# rc_switch_dualsided_with_fet_driver_2.net
KiCad netlist of a schematic drawn in EAGLE
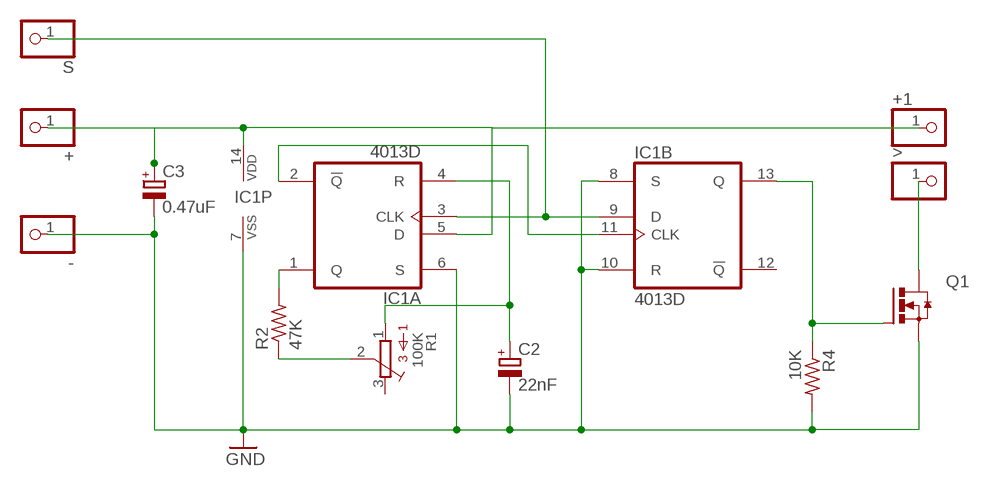
[diagram p0: schematic, sheet 1]

(export (version "E")
  (design (tool "Eeschema 10.0.6"))
  (components
    (comp (ref "+")
      (value "PINHD-1X1")
      (footprint "eagle-import:1X01")
      (libsource (lib "eagle-import") (part "PINHD-1X1"))
    )
    (comp (ref "+1")
      (value "PINHD-1X1")
      (footprint "eagle-import:1X01")
      (libsource (lib "eagle-import") (part "PINHD-1X1"))
    )
    (comp (ref "-")
      (value "PINHD-1X1")
      (footprint "eagle-import:1X01")
      (libsource (lib "eagle-import") (part "PINHD-1X1"))
    )
    (comp (ref ">")
      (value "PINHD-1X1")
      (footprint "eagle-import:1X01")
      (libsource (lib "eagle-import") (part "PINHD-1X1"))
    )
    (comp (ref "C2")
      (value "22nF")
      (footprint "eagle-import:PANASONIC_A")
      (libsource (lib "eagle-import") (part "CPOL-EUA"))
    )
    (comp (ref "C3")
      (value "0.47uF")
      (footprint "eagle-import:PANASONIC_A")
      (libsource (lib "eagle-import") (part "CPOL-EUA"))
    )
    (comp (ref "IC1")
      (value "4013D")
      (footprint "eagle-import:SO14")
      (libsource (lib "eagle-import") (part "4013D"))
    )
    (comp (ref "Q1")
      (value "HUF76629D3ST_F085D-PAK_TO252")
      (footprint "eagle-import:D-PAK_TO252")
      (libsource (lib "eagle-import") (part "HUF76629D3ST_F085D-PAK_TO252"))
    )
    (comp (ref "R1")
      (value "100K")
      (footprint "eagle-import:3386P")
      (libsource (lib "eagle-import") (part "3386-P"))
    )
    (comp (ref "R2")
      (value "47K")
      (footprint "eagle-import:R0805W")
      (libsource (lib "eagle-import") (part "R-US_R0805W"))
    )
    (comp (ref "R4")
      (value "10K")
      (footprint "eagle-import:R0805W")
      (libsource (lib "eagle-import") (part "R-US_R0805W"))
    )
    (comp (ref "S")
      (value "PINHD-1X1")
      (footprint "eagle-import:1X01")
      (libsource (lib "eagle-import") (part "PINHD-1X1"))
    )
  )
  (nets
    (net (code "1") (name "GND") (class "Default")
      (node (ref "-") (pin "1") (pinfunction "1_1") (pintype "passive"))
      (node (ref "C2") (pin "-") (pinfunction "-_-") (pintype "passive"))
      (node (ref "C3") (pin "-") (pinfunction "-_-") (pintype "passive"))
      (node (ref "IC1") (pin "10") (pinfunction "R_10") (pintype "input"))
      (node (ref "IC1") (pin "6") (pinfunction "S_6") (pintype "input"))
      (node (ref "IC1") (pin "7") (pinfunction "VSS_7") (pintype "power_in"))
      (node (ref "IC1") (pin "8") (pinfunction "S_8") (pintype "input"))
      (node (ref "Q1") (pin "3") (pinfunction "S_3") (pintype "passive"))
      (node (ref "R4") (pin "2") (pinfunction "2_2") (pintype "passive"))
    )
    (net (code "2") (name "Net-(IC1A-CLK)") (class "Default")
      (node (ref "IC1") (pin "3") (pinfunction "CLK_3") (pintype "input"))
      (node (ref "IC1") (pin "9") (pinfunction "D_9") (pintype "input"))
      (node (ref "S") (pin "1") (pinfunction "1_1") (pintype "passive"))
    )
    (net (code "3") (name "Net-(IC1A-D)") (class "Default")
      (node (ref "+") (pin "1") (pinfunction "1_1") (pintype "passive"))
      (node (ref "+1") (pin "1") (pinfunction "1_1") (pintype "passive"))
      (node (ref "C3") (pin "+") (pinfunction "+_+") (pintype "passive"))
      (node (ref "IC1") (pin "14") (pinfunction "VDD_14") (pintype "power_in"))
      (node (ref "IC1") (pin "5") (pinfunction "D_5") (pintype "input"))
    )
    (net (code "4") (name "Net-(IC1A-Q)") (class "Default")
      (node (ref "IC1") (pin "1") (pinfunction "Q_1") (pintype "output"))
      (node (ref "R2") (pin "2") (pinfunction "2_2") (pintype "passive"))
    )
    (net (code "5") (name "Net-(IC1A-R)") (class "Default")
      (node (ref "C2") (pin "+") (pinfunction "+_+") (pintype "passive"))
      (node (ref "IC1") (pin "4") (pinfunction "R_4") (pintype "input"))
      (node (ref "R1") (pin "1") (pinfunction "1_1") (pintype "passive"))
    )
    (net (code "6") (name "Net-(IC1A-~{Q})") (class "Default")
      (node (ref "IC1") (pin "11") (pinfunction "CLK_11") (pintype "input"))
      (node (ref "IC1") (pin "2") (pinfunction "~{Q}_2") (pintype "output"))
    )
    (net (code "7") (name "Net-(IC1B-Q)") (class "Default")
      (node (ref "IC1") (pin "13") (pinfunction "Q_13") (pintype "output"))
      (node (ref "Q1") (pin "1") (pinfunction "G_1") (pintype "passive"))
      (node (ref "R4") (pin "1") (pinfunction "1_1") (pintype "passive"))
    )
    (net (code "8") (name "Net-(Q1-D)") (class "Default")
      (node (ref ">") (pin "1") (pinfunction "1_1") (pintype "passive"))
      (node (ref "Q1") (pin "4") (pinfunction "D_4") (pintype "passive"))
    )
    (net (code "9") (name "Net-(R1-Pad2)") (class "Default")
      (node (ref "R1") (pin "2") (pinfunction "2_2") (pintype "passive"))
      (node (ref "R2") (pin "1") (pinfunction "1_1") (pintype "passive"))
    )
    (net (code "10") (name "unconnected-(IC1B-~{Q}-Pad12)") (class "Default")
      (node (ref "IC1") (pin "12") (pinfunction "~{Q}_12") (pintype "output"))
    )
    (net (code "11") (name "unconnected-(R1-Pad3)") (class "Default")
      (node (ref "R1") (pin "3") (pinfunction "3_3") (pintype "passive"))
    )
  )
)
